# 7segement3digits1badidea-mk-1_1.net
KiCad netlist of a schematic drawn in EAGLE
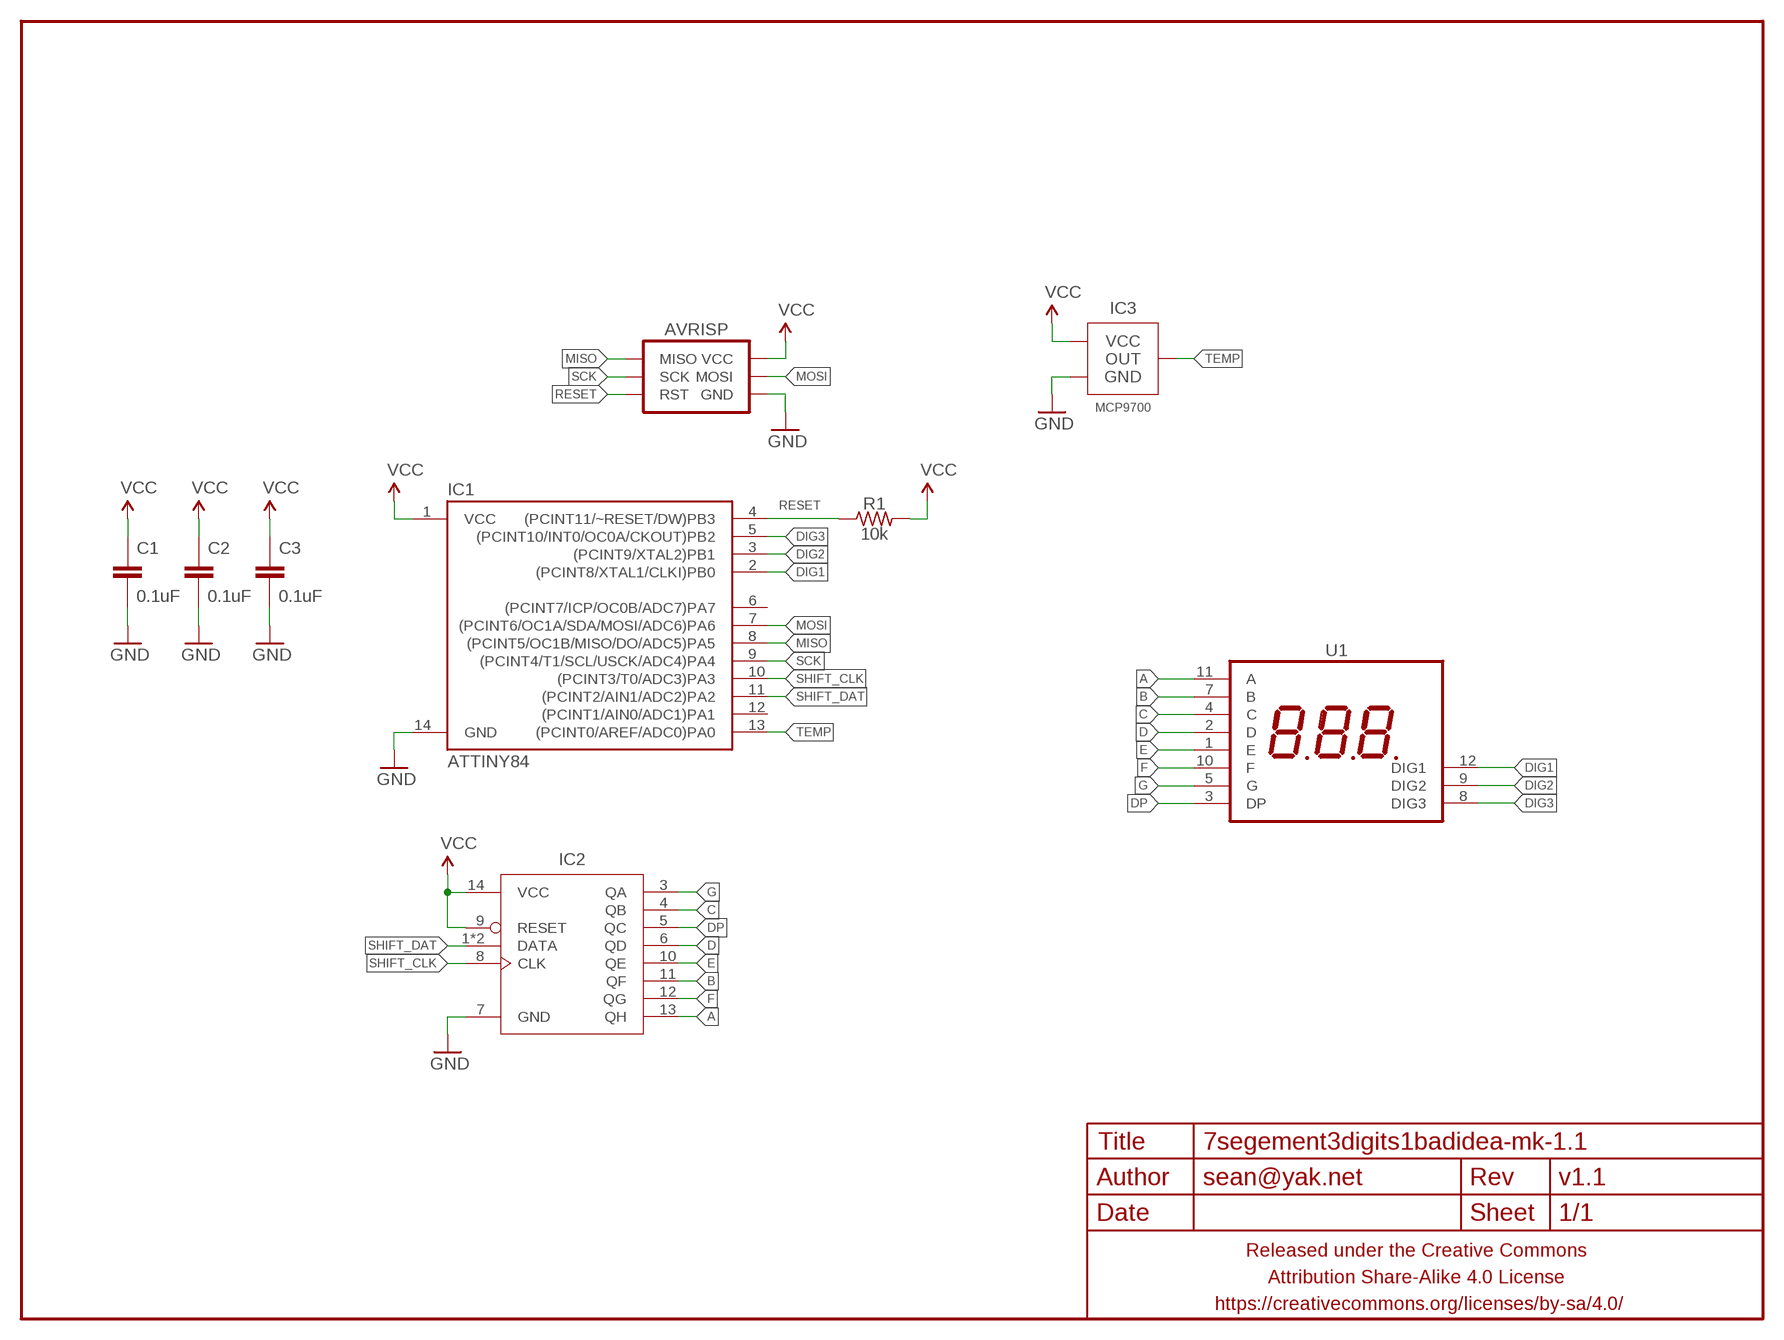
[diagram p0: schematic, sheet 1]

(export (version "E")
  (design (tool "Eeschema 10.0.6"))
  (components
    (comp (ref "AVRISP")
      (value "AVR_SPI_PRG_6PTH_INLINE_I2C")
      (footprint "eagle-import:AVR_ISP_INLINE_PTH_I2C")
      (libsource (lib "eagle-import") (part "AVR_SPI_PRG_6PTH_INLINE_I2C"))
    )
    (comp (ref "C1")
      (value "0.1uF")
      (footprint "eagle-import:C0603")
      (libsource (lib "eagle-import") (part "CAPACITOR-CERAMICC0603"))
    )
    (comp (ref "C2")
      (value "0.1uF")
      (footprint "eagle-import:C0603")
      (libsource (lib "eagle-import") (part "CAPACITOR-CERAMICC0603"))
    )
    (comp (ref "C3")
      (value "0.1uF")
      (footprint "eagle-import:C0603")
      (libsource (lib "eagle-import") (part "CAPACITOR-CERAMICC0603"))
    )
    (comp (ref "FRAME1")
      (value "FRAME-LETTERNO_PACKAGE")
      (footprint "eagle-import:DUMMY")
      (fields (field (name "DESIGNER") "sean@yak.net") (field (name "VERSION") "v1.1"))
      (libsource (lib "eagle-import") (part "FRAME-LETTERNO_PACKAGE"))
    )
    (comp (ref "IC1")
      (value "ATTINY84")
      (footprint "eagle-import:SO14")
      (libsource (lib "eagle-import") (part "ATTINY84"))
    )
    (comp (ref "IC2")
      (value "74HC164")
      (footprint "eagle-import:SO14")
      (libsource (lib "eagle-import") (part "74164SOIC"))
    )
    (comp (ref "IC3")
      (value "MCP9700")
      (footprint "eagle-import:TO-92-AMMO")
      (libsource (lib "eagle-import") (part "MCP9700TO-92-AMMO"))
    )
    (comp (ref "R1")
      (value "10k")
      (footprint "eagle-import:R0603")
      (libsource (lib "eagle-import") (part "RESISTORR0603"))
    )
    (comp (ref "U1")
      (value "7SEG_3DIGIT")
      (footprint "eagle-import:7SEG_3DIG_0.56IN")
      (libsource (lib "eagle-import") (part "7SEG_3DIGIT"))
    )
  )
  (nets
    (net (code "1") (name "A") (class "Default")
      (node (ref "IC2") (pin "13") (pinfunction "QH_13") (pintype "bidirectional"))
      (node (ref "U1") (pin "11") (pinfunction "A_11") (pintype "passive"))
    )
    (net (code "2") (name "B") (class "Default")
      (node (ref "IC2") (pin "11") (pinfunction "QF_11") (pintype "bidirectional"))
      (node (ref "U1") (pin "7") (pinfunction "B_7") (pintype "passive"))
    )
    (net (code "3") (name "C") (class "Default")
      (node (ref "IC2") (pin "4") (pinfunction "QB_4") (pintype "bidirectional"))
      (node (ref "U1") (pin "4") (pinfunction "C_4") (pintype "passive"))
    )
    (net (code "4") (name "D") (class "Default")
      (node (ref "IC2") (pin "6") (pinfunction "QD_6") (pintype "bidirectional"))
      (node (ref "U1") (pin "2") (pinfunction "D_2") (pintype "passive"))
    )
    (net (code "5") (name "DIG1") (class "Default")
      (node (ref "IC1") (pin "2") (pinfunction "(PCINT8/XTAL1/CLKI)PB0_2") (pintype "bidirectional"))
      (node (ref "U1") (pin "12") (pinfunction "DIG1_12") (pintype "passive"))
    )
    (net (code "6") (name "DIG2") (class "Default")
      (node (ref "IC1") (pin "3") (pinfunction "(PCINT9/XTAL2)PB1_3") (pintype "bidirectional"))
      (node (ref "U1") (pin "9") (pinfunction "DIG2_9") (pintype "passive"))
    )
    (net (code "7") (name "DIG3") (class "Default")
      (node (ref "IC1") (pin "5") (pinfunction "(PCINT10/INT0/OC0A/CKOUT)PB2_5") (pintype "bidirectional"))
      (node (ref "U1") (pin "8") (pinfunction "DIG3_8") (pintype "passive"))
    )
    (net (code "8") (name "DP") (class "Default")
      (node (ref "IC2") (pin "5") (pinfunction "QC_5") (pintype "bidirectional"))
      (node (ref "U1") (pin "3") (pinfunction "DP_3") (pintype "passive"))
    )
    (net (code "9") (name "E") (class "Default")
      (node (ref "IC2") (pin "10") (pinfunction "QE_10") (pintype "bidirectional"))
      (node (ref "U1") (pin "1") (pinfunction "E_1") (pintype "passive"))
    )
    (net (code "10") (name "F") (class "Default")
      (node (ref "IC2") (pin "12") (pinfunction "QG_12") (pintype "bidirectional"))
      (node (ref "U1") (pin "10") (pinfunction "F_10") (pintype "passive"))
    )
    (net (code "11") (name "G") (class "Default")
      (node (ref "IC2") (pin "3") (pinfunction "QA_3") (pintype "bidirectional"))
      (node (ref "U1") (pin "5") (pinfunction "G_5") (pintype "passive"))
    )
    (net (code "12") (name "GND") (class "Default")
      (node (ref "AVRISP") (pin "GND") (pinfunction "GND_GND") (pintype "passive"))
      (node (ref "C1") (pin "2") (pinfunction "2_2") (pintype "passive"))
      (node (ref "C2") (pin "2") (pinfunction "2_2") (pintype "passive"))
      (node (ref "C3") (pin "2") (pinfunction "2_2") (pintype "passive"))
      (node (ref "IC1") (pin "14") (pinfunction "GND_14") (pintype "bidirectional"))
      (node (ref "IC2") (pin "7") (pinfunction "GND_7") (pintype "bidirectional"))
      (node (ref "IC3") (pin "3") (pinfunction "GND_3") (pintype "bidirectional"))
    )
    (net (code "13") (name "MISO") (class "Default")
      (node (ref "AVRISP") (pin "MISO") (pinfunction "MISO_MISO") (pintype "passive"))
      (node (ref "IC1") (pin "8") (pinfunction "(PCINT5/OC1B/MISO/DO/ADC5)PA5_8") (pintype "bidirectional"))
    )
    (net (code "14") (name "MOSI") (class "Default")
      (node (ref "AVRISP") (pin "MOSI") (pinfunction "MOSI_MOSI") (pintype "passive"))
      (node (ref "IC1") (pin "7") (pinfunction "(PCINT6/OC1A/SDA/MOSI/ADC6)PA6_7") (pintype "bidirectional"))
    )
    (net (code "15") (name "RESET") (class "Default")
      (node (ref "AVRISP") (pin "RESET") (pinfunction "RST_RESET") (pintype "passive"))
      (node (ref "IC1") (pin "4") (pinfunction "(PCINT11/~{RESET/DW})PB3_4") (pintype "bidirectional"))
      (node (ref "R1") (pin "1") (pinfunction "1_1") (pintype "passive"))
    )
    (net (code "16") (name "SCK") (class "Default")
      (node (ref "AVRISP") (pin "SCK") (pinfunction "SCK_SCK") (pintype "passive"))
      (node (ref "IC1") (pin "9") (pinfunction "(PCINT4/T1/SCL/USCK/ADC4)PA4_9") (pintype "bidirectional"))
    )
    (net (code "17") (name "SHIFT_CLK") (class "Default")
      (node (ref "IC1") (pin "10") (pinfunction "(PCINT3/T0/ADC3)PA3_10") (pintype "bidirectional"))
      (node (ref "IC2") (pin "8") (pinfunction "CLK_8") (pintype "bidirectional"))
    )
    (net (code "18") (name "SHIFT_DAT") (class "Default")
      (node (ref "IC1") (pin "11") (pinfunction "(PCINT2/AIN1/ADC2)PA2_11") (pintype "bidirectional"))
      (node (ref "IC2") (pin "1") (pinfunction "DATA_1") (pintype "bidirectional"))
      (node (ref "IC2") (pin "2") (pinfunction "DATA_2") (pintype "bidirectional"))
    )
    (net (code "19") (name "TEMP") (class "Default")
      (node (ref "IC1") (pin "13") (pinfunction "(PCINT0/AREF/ADC0)PA0_13") (pintype "bidirectional"))
      (node (ref "IC3") (pin "2") (pinfunction "OUT_2") (pintype "bidirectional"))
    )
    (net (code "20") (name "VCC") (class "Default")
      (node (ref "AVRISP") (pin "VCC") (pinfunction "VCC_VCC") (pintype "passive"))
      (node (ref "C1") (pin "1") (pinfunction "1_1") (pintype "passive"))
      (node (ref "C2") (pin "1") (pinfunction "1_1") (pintype "passive"))
      (node (ref "C3") (pin "1") (pinfunction "1_1") (pintype "passive"))
      (node (ref "IC1") (pin "1") (pinfunction "VCC_1") (pintype "bidirectional"))
      (node (ref "IC2") (pin "14") (pinfunction "VCC_14") (pintype "bidirectional"))
      (node (ref "IC2") (pin "9") (pinfunction "RESET_9") (pintype "bidirectional"))
      (node (ref "IC3") (pin "1") (pinfunction "VCC_1") (pintype "bidirectional"))
      (node (ref "R1") (pin "2") (pinfunction "2_2") (pintype "passive"))
    )
    (net (code "21") (name "unconnected-(IC1-(PCINT1{slash}AIN0{slash}ADC1)PA1-Pad12)") (class "Default")
      (node (ref "IC1") (pin "12") (pinfunction "(PCINT1/AIN0/ADC1)PA1_12") (pintype "bidirectional"))
    )
    (net (code "22") (name "unconnected-(IC1-(PCINT7{slash}ICP{slash}OC0B{slash}ADC7)PA7-Pad6)") (class "Default")
      (node (ref "IC1") (pin "6") (pinfunction "(PCINT7/ICP/OC0B/ADC7)PA7_6") (pintype "bidirectional"))
    )
  )
)
